# SMS.net
KiCad netlist of a schematic drawn in Altium Designer
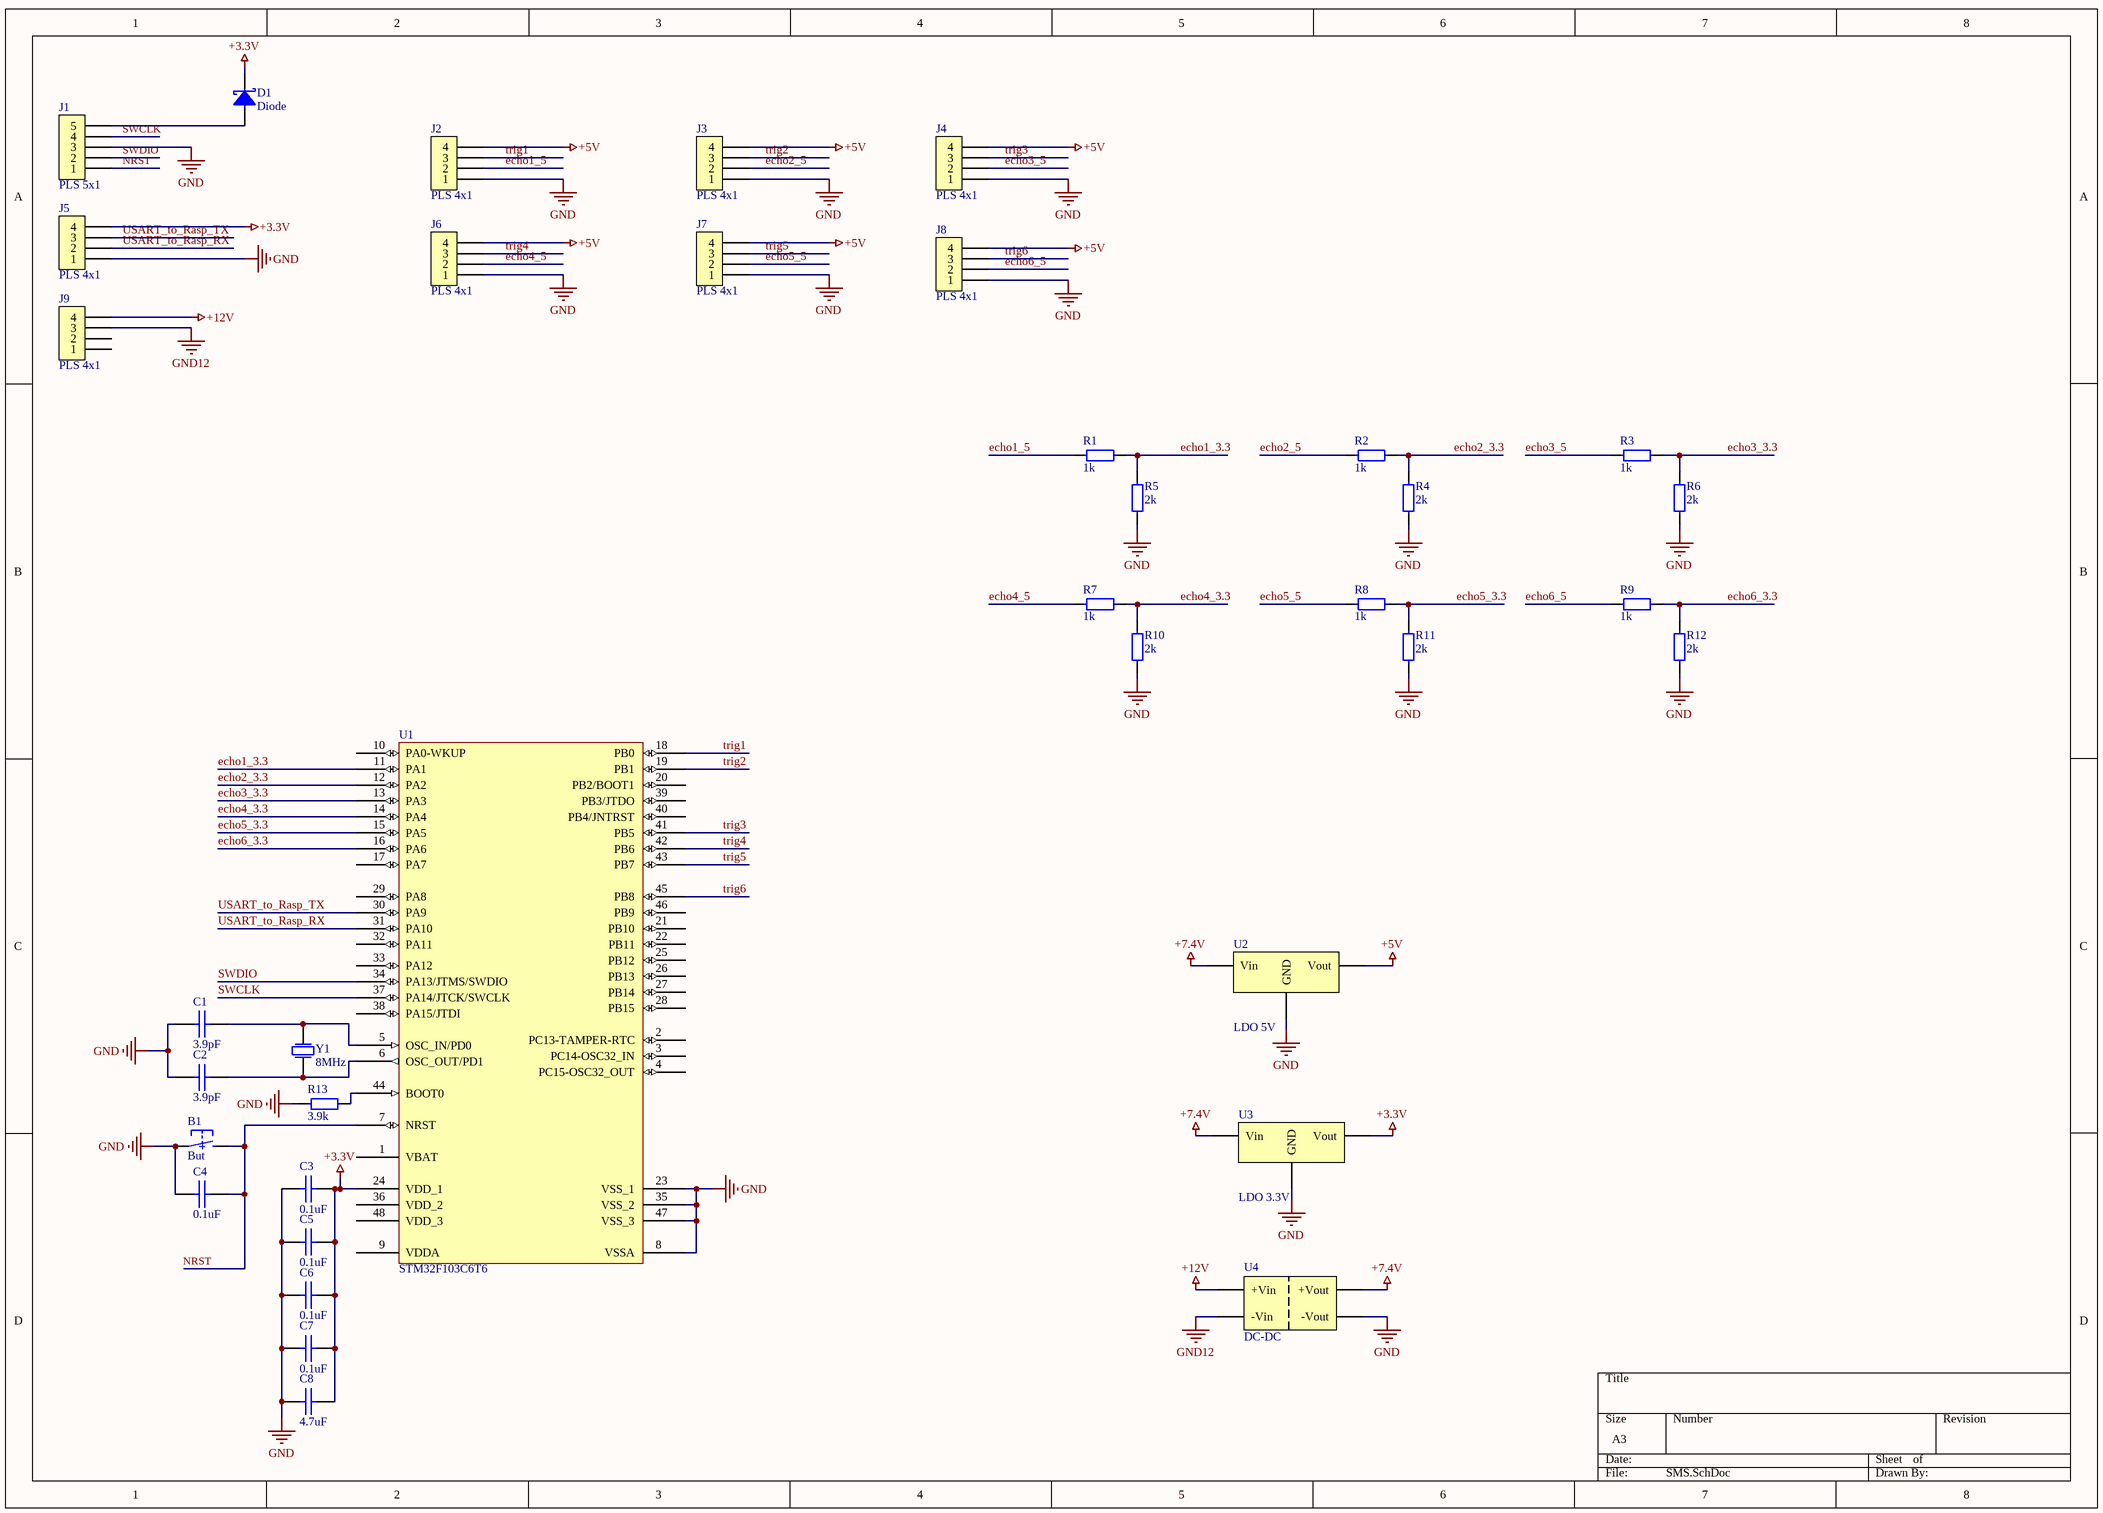
[diagram p0: SMS.SchDoc]

(export (version "E")
  (design (tool "Eeschema 10.0.6"))
  (components
    (comp (ref "B1")
      (value "But")
      (footprint "BUTTON 6x3.5")
      (description "Button 2 Conn SMD")
      (libsource (lib "RoboCor") (part "Button"))
    )
    (comp (ref "C1")
      (value "3.9pF")
      (footprint "0805 Capicator")
      (libsource (lib "RoboCor") (part "Cap 39pF"))
    )
    (comp (ref "C2")
      (value "3.9pF")
      (footprint "0805 Capicator")
      (libsource (lib "RoboCor") (part "Cap 39pF"))
    )
    (comp (ref "C3")
      (value "0.1uF")
      (footprint "0805 Capicator")
      (libsource (lib "RoboCor") (part "Cap 0.1uF"))
    )
    (comp (ref "C4")
      (value "0.1uF")
      (footprint "0805 Capicator")
      (libsource (lib "RoboCor") (part "Cap 0.1uF"))
    )
    (comp (ref "C5")
      (value "0.1uF")
      (footprint "0805 Capicator")
      (libsource (lib "RoboCor") (part "Cap 0.1uF"))
    )
    (comp (ref "C6")
      (value "0.1uF")
      (footprint "0805 Capicator")
      (libsource (lib "RoboCor") (part "Cap 0.1uF"))
    )
    (comp (ref "C7")
      (value "0.1uF")
      (footprint "0805 Capicator")
      (libsource (lib "RoboCor") (part "Cap 0.1uF"))
    )
    (comp (ref "C8")
      (value "4.7uF")
      (footprint "0805 Capicator")
      (libsource (lib "RoboCor") (part "Cap 4.7uF"))
    )
    (comp (ref "D1")
      (value "Diode")
      (footprint "sod-123")
      (description "0.5 A, Low Forward Voltage less than 385 mV, 400 mW Power Dissipation Package")
      (libsource (lib "RoboCor") (part "Diode Schottky"))
    )
    (comp (ref "J1")
      (value "PLS 5x1")
      (footprint "PLS 5x1")
      (description "Header, 5-Pin")
      (libsource (lib "RoboCor") (part "Conn 5"))
    )
    (comp (ref "J2")
      (value "PLS 4x1")
      (footprint "PLS 4x1")
      (description "Header, 4-Pin")
      (libsource (lib "RoboCor") (part "Conn 4"))
    )
    (comp (ref "J3")
      (value "PLS 4x1")
      (footprint "PLS 4x1")
      (description "Header, 4-Pin")
      (libsource (lib "RoboCor") (part "Conn 4"))
    )
    (comp (ref "J4")
      (value "PLS 4x1")
      (footprint "PLS 4x1")
      (description "Header, 4-Pin")
      (libsource (lib "RoboCor") (part "Conn 4"))
    )
    (comp (ref "J5")
      (value "PLS 4x1")
      (footprint "PLS 4x1")
      (description "Header, 4-Pin")
      (libsource (lib "RoboCor") (part "Conn 4"))
    )
    (comp (ref "J6")
      (value "PLS 4x1")
      (footprint "PLS 4x1")
      (description "Header, 4-Pin")
      (libsource (lib "RoboCor") (part "Conn 4"))
    )
    (comp (ref "J7")
      (value "PLS 4x1")
      (footprint "PLS 4x1")
      (description "Header, 4-Pin")
      (libsource (lib "RoboCor") (part "Conn 4"))
    )
    (comp (ref "J8")
      (value "PLS 4x1")
      (footprint "PLS 4x1")
      (description "Header, 4-Pin")
      (libsource (lib "RoboCor") (part "Conn 4"))
    )
    (comp (ref "J9")
      (value "PLS 4x1")
      (footprint "PLS 4x1")
      (description "Header, 4-Pin")
      (libsource (lib "RoboCor") (part "Conn 4"))
    )
    (comp (ref "R1") (value "1k") (footprint "0805 Resistor") (libsource (lib "RoboCor") (part "Res 1k")))
    (comp (ref "R2") (value "1k") (footprint "0805 Resistor") (libsource (lib "RoboCor") (part "Res 1k")))
    (comp (ref "R3") (value "1k") (footprint "0805 Resistor") (libsource (lib "RoboCor") (part "Res 1k")))
    (comp (ref "R4") (value "2k") (footprint "0805 Resistor") (libsource (lib "RoboCor") (part "Res 2k")))
    (comp (ref "R5") (value "2k") (footprint "0805 Resistor") (libsource (lib "RoboCor") (part "Res 2k")))
    (comp (ref "R6") (value "2k") (footprint "0805 Resistor") (libsource (lib "RoboCor") (part "Res 2k")))
    (comp (ref "R7") (value "1k") (footprint "0805 Resistor") (libsource (lib "RoboCor") (part "Res 1k")))
    (comp (ref "R8") (value "1k") (footprint "0805 Resistor") (libsource (lib "RoboCor") (part "Res 1k")))
    (comp (ref "R9") (value "1k") (footprint "0805 Resistor") (libsource (lib "RoboCor") (part "Res 1k")))
    (comp (ref "R10") (value "2k") (footprint "0805 Resistor") (libsource (lib "RoboCor") (part "Res 2k")))
    (comp (ref "R11") (value "2k") (footprint "0805 Resistor") (libsource (lib "RoboCor") (part "Res 2k")))
    (comp (ref "R12") (value "2k") (footprint "0805 Resistor") (libsource (lib "RoboCor") (part "Res 2k")))
    (comp (ref "R13")
      (value "3.9k")
      (footprint "0805 Resistor")
      (libsource (lib "RoboCor") (part "Res 3.9k"))
    )
    (comp (ref "U1")
      (value "STM32F103C6T6")
      (footprint "STM32F103C6T6")
      (libsource (lib "RoboCor") (part "STM32F103C6T6"))
    )
    (comp (ref "U2")
      (value "LDO 5V")
      (footprint "TO-252")
      (description "LDO Regulator Pos 5V 1A")
      (libsource (lib "RoboCor") (part "LDO 5V"))
    )
    (comp (ref "U3")
      (value "LDO 3.3V")
      (footprint "SOT-223")
      (description "LDO Regulator Pos 3.3V 1.3A 4-Pin(3+Tab) SOT-223 T/R")
      (libsource (lib "RoboCor") (part "LDO 3.3V"))
    )
    (comp (ref "U4") (value "DC-DC") (footprint "DC-DC") (libsource (lib "RoboCor") (part "DC-DC")))
    (comp (ref "Y1")
      (value "8MHz")
      (footprint "hc-49sm")
      (description "Crystal. HC-49SM (US)")
      (libsource (lib "RoboCor") (part "Crystal 8MHz"))
    )
  )
  (nets
    (net (code "1") (name "+3.3V") (class "Default")
      (node (ref "C3") (pin "2") (pinfunction "2_2") (pintype "passive"))
      (node (ref "C5") (pin "2") (pinfunction "2_2") (pintype "passive"))
      (node (ref "C6") (pin "2") (pinfunction "2_2") (pintype "passive"))
      (node (ref "C7") (pin "2") (pinfunction "2_2") (pintype "passive"))
      (node (ref "C8") (pin "2") (pinfunction "2_2") (pintype "passive"))
      (node (ref "D1") (pin "2") (pinfunction "2_2") (pintype "passive"))
      (node (ref "J5") (pin "4") (pinfunction "4_4") (pintype "passive"))
      (node (ref "U1") (pin "24") (pinfunction "VDD_1_24") (pintype "power_in"))
      (node (ref "U3") (pin "2") (pinfunction "Vout_2") (pintype "power_in"))
    )
    (net (code "2") (name "+5V") (class "Default")
      (node (ref "J2") (pin "4") (pinfunction "4_4") (pintype "passive"))
      (node (ref "J3") (pin "4") (pinfunction "4_4") (pintype "passive"))
      (node (ref "J4") (pin "4") (pinfunction "4_4") (pintype "passive"))
      (node (ref "J6") (pin "4") (pinfunction "4_4") (pintype "passive"))
      (node (ref "J7") (pin "4") (pinfunction "4_4") (pintype "passive"))
      (node (ref "J8") (pin "4") (pinfunction "4_4") (pintype "passive"))
      (node (ref "U2") (pin "2") (pinfunction "Vout_2") (pintype "power_in"))
    )
    (net (code "3") (name "+7.4V") (class "Default")
      (node (ref "U2") (pin "3") (pinfunction "Vin_3") (pintype "power_in"))
      (node (ref "U3") (pin "3") (pinfunction "Vin_3") (pintype "power_in"))
      (node (ref "U4") (pin "3") (pinfunction "+Vout_3") (pintype "power_in"))
    )
    (net (code "4") (name "+12V") (class "Default")
      (node (ref "J9") (pin "4") (pinfunction "4_4") (pintype "passive"))
      (node (ref "U4") (pin "1") (pinfunction "+Vin_1") (pintype "power_in"))
    )
    (net (code "5") (name "/NRST") (class "Default")
      (node (ref "B1") (pin "2") (pinfunction "2_2") (pintype "passive"))
      (node (ref "C4") (pin "2") (pinfunction "2_2") (pintype "passive"))
      (node (ref "J1") (pin "1") (pinfunction "1_1") (pintype "passive"))
      (node (ref "U1") (pin "7") (pinfunction "NRST_7") (pintype "bidirectional"))
    )
    (net (code "6") (name "/SWCLK") (class "Default")
      (node (ref "J1") (pin "4") (pinfunction "4_4") (pintype "passive"))
      (node (ref "U1") (pin "37") (pinfunction "PA14/JTCK/SWCLK_37") (pintype "bidirectional"))
    )
    (net (code "7") (name "/SWDIO") (class "Default")
      (node (ref "J1") (pin "2") (pinfunction "2_2") (pintype "passive"))
      (node (ref "U1") (pin "34") (pinfunction "PA13/JTMS/SWDIO_34") (pintype "bidirectional"))
    )
    (net (code "8") (name "/USART_to_Rasp_RX") (class "Default")
      (node (ref "J5") (pin "2") (pinfunction "2_2") (pintype "passive"))
      (node (ref "U1") (pin "31") (pinfunction "PA10_31") (pintype "bidirectional"))
    )
    (net (code "9") (name "/USART_to_Rasp_TX") (class "Default")
      (node (ref "J5") (pin "3") (pinfunction "3_3") (pintype "passive"))
      (node (ref "U1") (pin "30") (pinfunction "PA9_30") (pintype "bidirectional"))
    )
    (net (code "10") (name "/echo1_3.3") (class "Default")
      (node (ref "R1") (pin "2") (pinfunction "2_2") (pintype "passive"))
      (node (ref "R5") (pin "2") (pinfunction "2_2") (pintype "passive"))
      (node (ref "U1") (pin "11") (pinfunction "PA1_11") (pintype "bidirectional"))
    )
    (net (code "11") (name "/echo1_5") (class "Default")
      (node (ref "J2") (pin "2") (pinfunction "2_2") (pintype "passive"))
      (node (ref "R1") (pin "1") (pinfunction "1_1") (pintype "passive"))
    )
    (net (code "12") (name "/echo2_3.3") (class "Default")
      (node (ref "R2") (pin "2") (pinfunction "2_2") (pintype "passive"))
      (node (ref "R4") (pin "2") (pinfunction "2_2") (pintype "passive"))
      (node (ref "U1") (pin "12") (pinfunction "PA2_12") (pintype "bidirectional"))
    )
    (net (code "13") (name "/echo2_5") (class "Default")
      (node (ref "J3") (pin "2") (pinfunction "2_2") (pintype "passive"))
      (node (ref "R2") (pin "1") (pinfunction "1_1") (pintype "passive"))
    )
    (net (code "14") (name "/echo3_3.3") (class "Default")
      (node (ref "R3") (pin "2") (pinfunction "2_2") (pintype "passive"))
      (node (ref "R6") (pin "2") (pinfunction "2_2") (pintype "passive"))
      (node (ref "U1") (pin "13") (pinfunction "PA3_13") (pintype "bidirectional"))
    )
    (net (code "15") (name "/echo3_5") (class "Default")
      (node (ref "J4") (pin "2") (pinfunction "2_2") (pintype "passive"))
      (node (ref "R3") (pin "1") (pinfunction "1_1") (pintype "passive"))
    )
    (net (code "16") (name "/echo4_3.3") (class "Default")
      (node (ref "R10") (pin "2") (pinfunction "2_2") (pintype "passive"))
      (node (ref "R7") (pin "2") (pinfunction "2_2") (pintype "passive"))
      (node (ref "U1") (pin "14") (pinfunction "PA4_14") (pintype "bidirectional"))
    )
    (net (code "17") (name "/echo4_5") (class "Default")
      (node (ref "J6") (pin "2") (pinfunction "2_2") (pintype "passive"))
      (node (ref "R7") (pin "1") (pinfunction "1_1") (pintype "passive"))
    )
    (net (code "18") (name "/echo5_3.3") (class "Default")
      (node (ref "R11") (pin "2") (pinfunction "2_2") (pintype "passive"))
      (node (ref "R8") (pin "2") (pinfunction "2_2") (pintype "passive"))
      (node (ref "U1") (pin "15") (pinfunction "PA5_15") (pintype "bidirectional"))
    )
    (net (code "19") (name "/echo5_5") (class "Default")
      (node (ref "J7") (pin "2") (pinfunction "2_2") (pintype "passive"))
      (node (ref "R8") (pin "1") (pinfunction "1_1") (pintype "passive"))
    )
    (net (code "20") (name "/echo6_3.3") (class "Default")
      (node (ref "R12") (pin "2") (pinfunction "2_2") (pintype "passive"))
      (node (ref "R9") (pin "2") (pinfunction "2_2") (pintype "passive"))
      (node (ref "U1") (pin "16") (pinfunction "PA6_16") (pintype "bidirectional"))
    )
    (net (code "21") (name "/echo6_5") (class "Default")
      (node (ref "J8") (pin "2") (pinfunction "2_2") (pintype "passive"))
      (node (ref "R9") (pin "1") (pinfunction "1_1") (pintype "passive"))
    )
    (net (code "22") (name "/trig1") (class "Default")
      (node (ref "J2") (pin "3") (pinfunction "3_3") (pintype "passive"))
      (node (ref "U1") (pin "18") (pinfunction "PB0_18") (pintype "bidirectional"))
    )
    (net (code "23") (name "/trig2") (class "Default")
      (node (ref "J3") (pin "3") (pinfunction "3_3") (pintype "passive"))
      (node (ref "U1") (pin "19") (pinfunction "PB1_19") (pintype "bidirectional"))
    )
    (net (code "24") (name "/trig3") (class "Default")
      (node (ref "J4") (pin "3") (pinfunction "3_3") (pintype "passive"))
      (node (ref "U1") (pin "41") (pinfunction "PB5_41") (pintype "bidirectional"))
    )
    (net (code "25") (name "/trig4") (class "Default")
      (node (ref "J6") (pin "3") (pinfunction "3_3") (pintype "passive"))
      (node (ref "U1") (pin "42") (pinfunction "PB6_42") (pintype "bidirectional"))
    )
    (net (code "26") (name "/trig5") (class "Default")
      (node (ref "J7") (pin "3") (pinfunction "3_3") (pintype "passive"))
      (node (ref "U1") (pin "43") (pinfunction "PB7_43") (pintype "bidirectional"))
    )
    (net (code "27") (name "/trig6") (class "Default")
      (node (ref "J8") (pin "3") (pinfunction "3_3") (pintype "passive"))
      (node (ref "U1") (pin "45") (pinfunction "PB8_45") (pintype "bidirectional"))
    )
    (net (code "28") (name "GND") (class "Default")
      (node (ref "B1") (pin "1") (pinfunction "1_1") (pintype "passive"))
      (node (ref "C1") (pin "1") (pinfunction "1_1") (pintype "passive"))
      (node (ref "C2") (pin "1") (pinfunction "1_1") (pintype "passive"))
      (node (ref "C3") (pin "1") (pinfunction "1_1") (pintype "passive"))
      (node (ref "C4") (pin "1") (pinfunction "1_1") (pintype "passive"))
      (node (ref "C5") (pin "1") (pinfunction "1_1") (pintype "passive"))
      (node (ref "C6") (pin "1") (pinfunction "1_1") (pintype "passive"))
      (node (ref "C7") (pin "1") (pinfunction "1_1") (pintype "passive"))
      (node (ref "C8") (pin "1") (pinfunction "1_1") (pintype "passive"))
      (node (ref "J1") (pin "3") (pinfunction "3_3") (pintype "passive"))
      (node (ref "J2") (pin "1") (pinfunction "1_1") (pintype "passive"))
      (node (ref "J3") (pin "1") (pinfunction "1_1") (pintype "passive"))
      (node (ref "J4") (pin "1") (pinfunction "1_1") (pintype "passive"))
      (node (ref "J5") (pin "1") (pinfunction "1_1") (pintype "passive"))
      (node (ref "J6") (pin "1") (pinfunction "1_1") (pintype "passive"))
      (node (ref "J7") (pin "1") (pinfunction "1_1") (pintype "passive"))
      (node (ref "J8") (pin "1") (pinfunction "1_1") (pintype "passive"))
      (node (ref "R10") (pin "1") (pinfunction "1_1") (pintype "passive"))
      (node (ref "R11") (pin "1") (pinfunction "1_1") (pintype "passive"))
      (node (ref "R12") (pin "1") (pinfunction "1_1") (pintype "passive"))
      (node (ref "R13") (pin "1") (pinfunction "1_1") (pintype "passive"))
      (node (ref "R4") (pin "1") (pinfunction "1_1") (pintype "passive"))
      (node (ref "R5") (pin "1") (pinfunction "1_1") (pintype "passive"))
      (node (ref "R6") (pin "1") (pinfunction "1_1") (pintype "passive"))
      (node (ref "U1") (pin "23") (pinfunction "VSS_1_23") (pintype "power_in"))
      (node (ref "U1") (pin "35") (pinfunction "VSS_2_35") (pintype "power_in"))
      (node (ref "U1") (pin "47") (pinfunction "VSS_3_47") (pintype "power_in"))
      (node (ref "U1") (pin "8") (pinfunction "VSSA_8") (pintype "power_in"))
      (node (ref "U2") (pin "1") (pinfunction "GND_1") (pintype "power_in"))
      (node (ref "U3") (pin "1") (pinfunction "GND_1") (pintype "power_in"))
      (node (ref "U4") (pin "4") (pinfunction "-Vout_4") (pintype "power_in"))
    )
    (net (code "29") (name "GND12") (class "Default")
      (node (ref "J9") (pin "3") (pinfunction "3_3") (pintype "passive"))
      (node (ref "U4") (pin "2") (pinfunction "-Vin_2") (pintype "power_in"))
    )
    (net (code "30") (name "Net-(D1-Pad1)") (class "Default")
      (node (ref "D1") (pin "1") (pinfunction "1_1") (pintype "passive"))
      (node (ref "J1") (pin "5") (pinfunction "5_5") (pintype "passive"))
    )
    (net (code "31") (name "Net-(U1-BOOT0)") (class "Default")
      (node (ref "R13") (pin "2") (pinfunction "2_2") (pintype "passive"))
      (node (ref "U1") (pin "44") (pinfunction "BOOT0_44") (pintype "input"))
    )
    (net (code "32") (name "Net-(U1-OSC_IN{slash}PD0)") (class "Default")
      (node (ref "C1") (pin "2") (pinfunction "2_2") (pintype "passive"))
      (node (ref "U1") (pin "5") (pinfunction "OSC_IN/PD0_5") (pintype "input"))
      (node (ref "Y1") (pin "2") (pinfunction "2_2") (pintype "passive"))
    )
    (net (code "33") (name "Net-(U1-OSC_OUT{slash}PD1)") (class "Default")
      (node (ref "C2") (pin "2") (pinfunction "2_2") (pintype "passive"))
      (node (ref "U1") (pin "6") (pinfunction "OSC_OUT/PD1_6") (pintype "output"))
      (node (ref "Y1") (pin "1") (pinfunction "1_1") (pintype "passive"))
    )
    (net (code "34") (name "unconnected-(J9-Pad1)") (class "Default")
      (node (ref "J9") (pin "1") (pinfunction "1_1") (pintype "passive"))
    )
    (net (code "35") (name "unconnected-(J9-Pad2)") (class "Default")
      (node (ref "J9") (pin "2") (pinfunction "2_2") (pintype "passive"))
    )
    (net (code "36") (name "unconnected-(U1-PA0-WKUP-Pad10)") (class "Default")
      (node (ref "U1") (pin "10") (pinfunction "PA0-WKUP_10") (pintype "bidirectional"))
    )
    (net (code "37") (name "unconnected-(U1-PA7-Pad17)") (class "Default")
      (node (ref "U1") (pin "17") (pinfunction "PA7_17") (pintype "bidirectional"))
    )
    (net (code "38") (name "unconnected-(U1-PA8-Pad29)") (class "Default")
      (node (ref "U1") (pin "29") (pinfunction "PA8_29") (pintype "bidirectional"))
    )
    (net (code "39") (name "unconnected-(U1-PA11-Pad32)") (class "Default")
      (node (ref "U1") (pin "32") (pinfunction "PA11_32") (pintype "bidirectional"))
    )
    (net (code "40") (name "unconnected-(U1-PA12-Pad33)") (class "Default")
      (node (ref "U1") (pin "33") (pinfunction "PA12_33") (pintype "bidirectional"))
    )
    (net (code "41") (name "unconnected-(U1-PA15{slash}JTDI-Pad38)") (class "Default")
      (node (ref "U1") (pin "38") (pinfunction "PA15/JTDI_38") (pintype "bidirectional"))
    )
    (net (code "42") (name "unconnected-(U1-PB2{slash}BOOT1-Pad20)") (class "Default")
      (node (ref "U1") (pin "20") (pinfunction "PB2/BOOT1_20") (pintype "bidirectional"))
    )
    (net (code "43") (name "unconnected-(U1-PB3{slash}JTDO-Pad39)") (class "Default")
      (node (ref "U1") (pin "39") (pinfunction "PB3/JTDO_39") (pintype "bidirectional"))
    )
    (net (code "44") (name "unconnected-(U1-PB4{slash}JNTRST-Pad40)") (class "Default")
      (node (ref "U1") (pin "40") (pinfunction "PB4/JNTRST_40") (pintype "bidirectional"))
    )
    (net (code "45") (name "unconnected-(U1-PB9-Pad46)") (class "Default")
      (node (ref "U1") (pin "46") (pinfunction "PB9_46") (pintype "bidirectional"))
    )
    (net (code "46") (name "unconnected-(U1-PB10-Pad21)") (class "Default")
      (node (ref "U1") (pin "21") (pinfunction "PB10_21") (pintype "bidirectional"))
    )
    (net (code "47") (name "unconnected-(U1-PB11-Pad22)") (class "Default")
      (node (ref "U1") (pin "22") (pinfunction "PB11_22") (pintype "bidirectional"))
    )
    (net (code "48") (name "unconnected-(U1-PB12-Pad25)") (class "Default")
      (node (ref "U1") (pin "25") (pinfunction "PB12_25") (pintype "bidirectional"))
    )
    (net (code "49") (name "unconnected-(U1-PB13-Pad26)") (class "Default")
      (node (ref "U1") (pin "26") (pinfunction "PB13_26") (pintype "bidirectional"))
    )
    (net (code "50") (name "unconnected-(U1-PB14-Pad27)") (class "Default")
      (node (ref "U1") (pin "27") (pinfunction "PB14_27") (pintype "bidirectional"))
    )
    (net (code "51") (name "unconnected-(U1-PB15-Pad28)") (class "Default")
      (node (ref "U1") (pin "28") (pinfunction "PB15_28") (pintype "bidirectional"))
    )
    (net (code "52") (name "unconnected-(U1-PC13-TAMPER-RTC-Pad2)") (class "Default")
      (node (ref "U1") (pin "2") (pinfunction "PC13-TAMPER-RTC_2") (pintype "bidirectional"))
    )
    (net (code "53") (name "unconnected-(U1-PC14-OSC32_IN-Pad3)") (class "Default")
      (node (ref "U1") (pin "3") (pinfunction "PC14-OSC32_IN_3") (pintype "bidirectional"))
    )
    (net (code "54") (name "unconnected-(U1-PC15-OSC32_OUT-Pad4)") (class "Default")
      (node (ref "U1") (pin "4") (pinfunction "PC15-OSC32_OUT_4") (pintype "bidirectional"))
    )
    (net (code "55") (name "unconnected-(U1-VBAT-Pad1)") (class "Default")
      (node (ref "U1") (pin "1") (pinfunction "VBAT_1") (pintype "power_in"))
    )
    (net (code "56") (name "unconnected-(U1-VDDA-Pad9)") (class "Default")
      (node (ref "U1") (pin "9") (pinfunction "VDDA_9") (pintype "power_in"))
    )
    (net (code "57") (name "unconnected-(U1-VDD_2-Pad36)") (class "Default")
      (node (ref "U1") (pin "36") (pinfunction "VDD_2_36") (pintype "power_in"))
    )
    (net (code "58") (name "unconnected-(U1-VDD_3-Pad48)") (class "Default")
      (node (ref "U1") (pin "48") (pinfunction "VDD_3_48") (pintype "power_in"))
    )
  )
)
